# BluetoothBoard.net
KiCad netlist of a schematic drawn in EAGLE
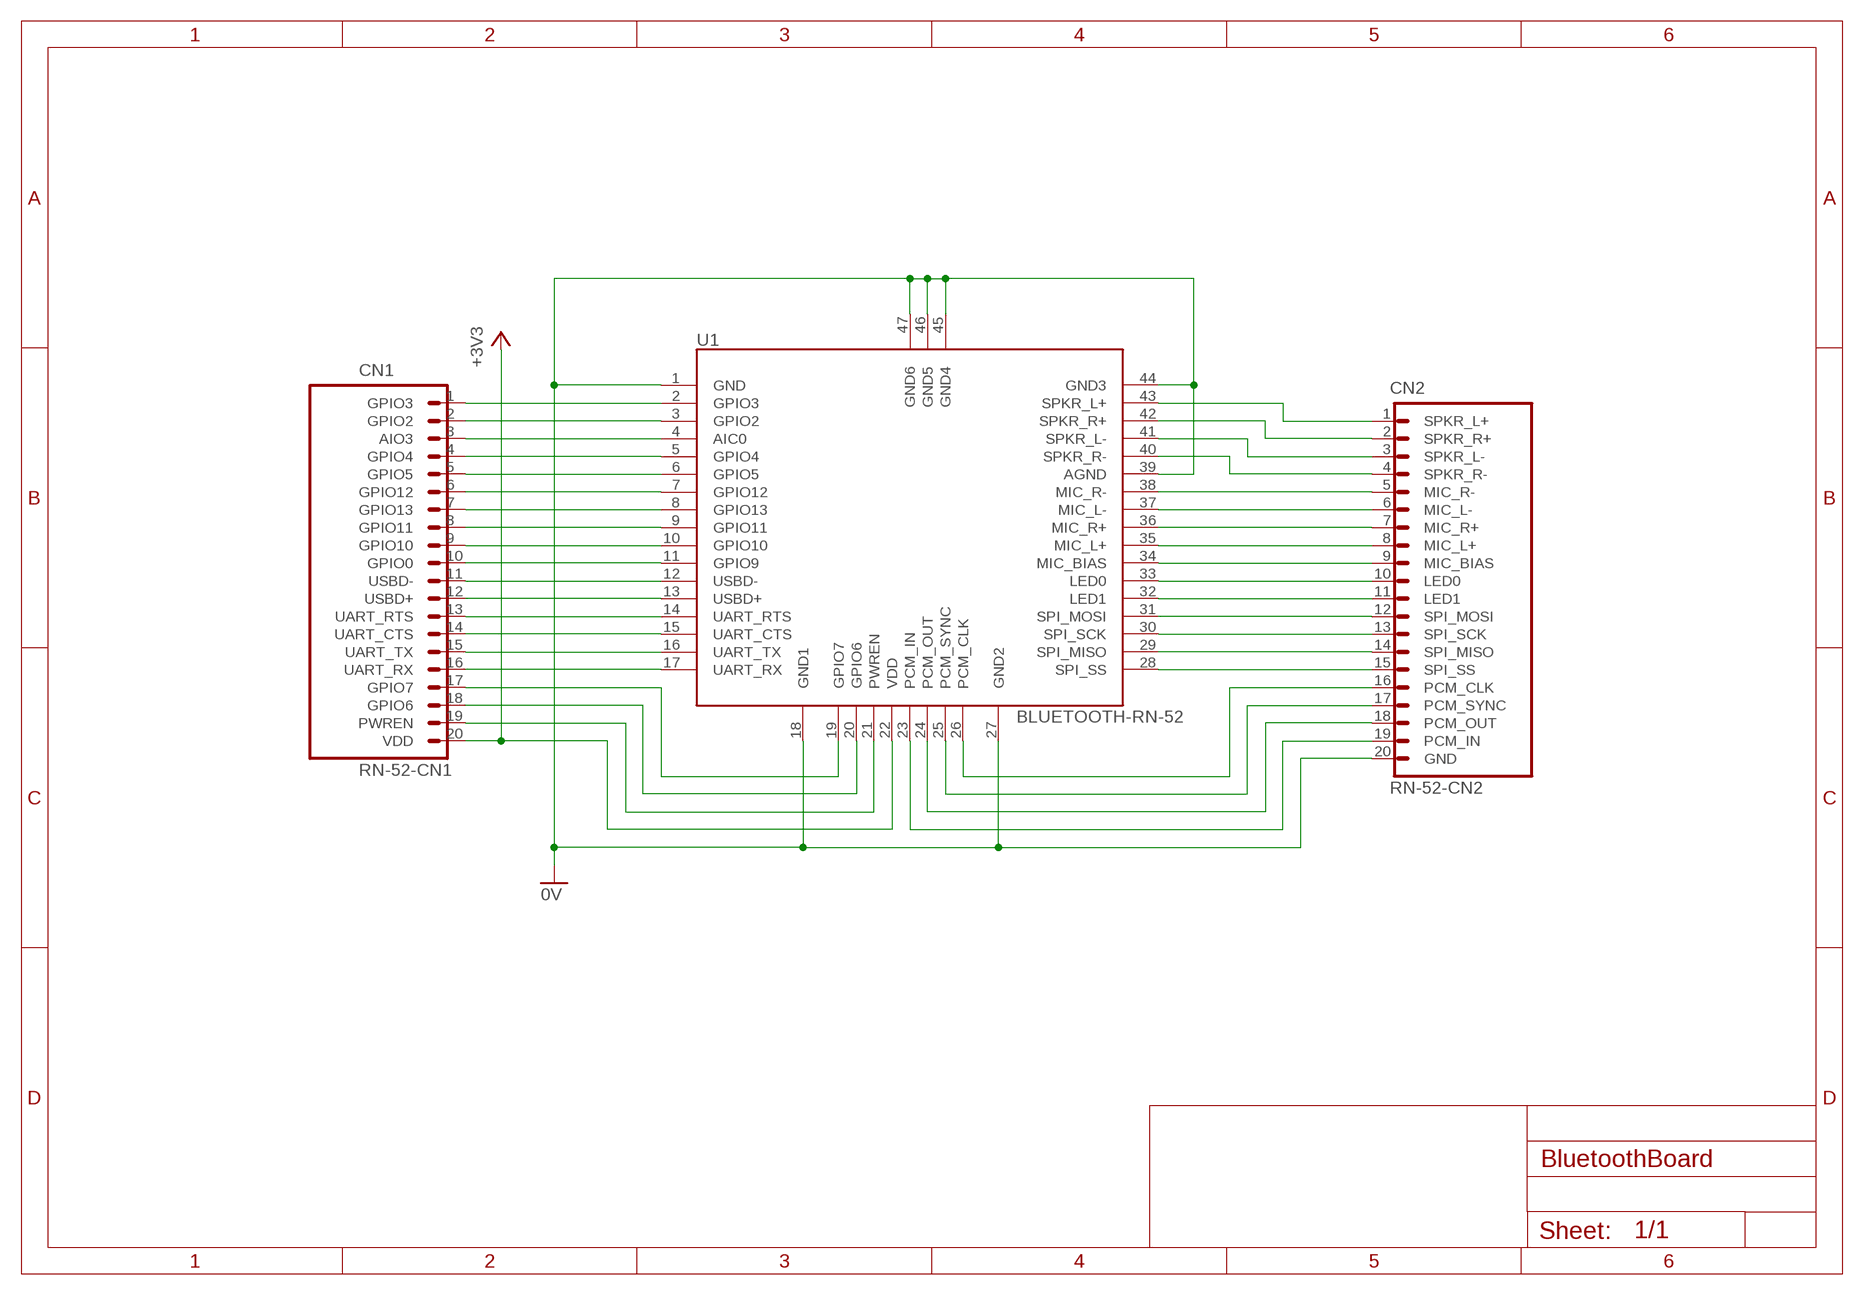
[diagram p0: schematic, sheet 1]

(export (version "E")
  (design (tool "Eeschema 10.0.6"))
  (components
    (comp (ref "CN1")
      (value "RN-52-CN1")
      (footprint "eagle-import:RN-52-CN1")
      (libsource (lib "eagle-import") (part "RN-52-CN1"))
    )
    (comp (ref "CN2")
      (value "RN-52-CN2")
      (footprint "eagle-import:RN-52-CN2")
      (libsource (lib "eagle-import") (part "RN-52-CN2"))
    )
    (comp (ref "U1")
      (value "BLUETOOTH-RN-52")
      (footprint "eagle-import:RN-52")
      (libsource (lib "eagle-import") (part "BLUETOOTH-RN-52"))
    )
  )
  (nets
    (net (code "1") (name "+3V3") (class "Default")
      (node (ref "CN1") (pin "20") (pinfunction "VDD_20") (pintype "bidirectional"))
      (node (ref "U1") (pin "22") (pinfunction "VDD_22") (pintype "passive"))
    )
    (net (code "2") (name "0V") (class "Default")
      (node (ref "CN2") (pin "20") (pinfunction "GND_20") (pintype "bidirectional"))
      (node (ref "U1") (pin "1") (pinfunction "GND_1") (pintype "passive"))
      (node (ref "U1") (pin "18") (pinfunction "GND1_18") (pintype "passive"))
      (node (ref "U1") (pin "27") (pinfunction "GND2_27") (pintype "passive"))
      (node (ref "U1") (pin "39") (pinfunction "AGND_39") (pintype "passive"))
      (node (ref "U1") (pin "44") (pinfunction "GND3_44") (pintype "passive"))
      (node (ref "U1") (pin "45") (pinfunction "GND4_45") (pintype "passive"))
      (node (ref "U1") (pin "46") (pinfunction "GND5_46") (pintype "passive"))
      (node (ref "U1") (pin "47") (pinfunction "GND6_47") (pintype "passive"))
    )
    (net (code "3") (name "Net-(CN1-AIO3)") (class "Default")
      (node (ref "CN1") (pin "3") (pinfunction "AIO3_3") (pintype "bidirectional"))
      (node (ref "U1") (pin "4") (pinfunction "AIC0_4") (pintype "bidirectional"))
    )
    (net (code "4") (name "Net-(CN1-GPIO0)") (class "Default")
      (node (ref "CN1") (pin "10") (pinfunction "GPIO0_10") (pintype "bidirectional"))
      (node (ref "U1") (pin "11") (pinfunction "GPIO9_11") (pintype "bidirectional"))
    )
    (net (code "5") (name "Net-(CN1-GPIO2)") (class "Default")
      (node (ref "CN1") (pin "2") (pinfunction "GPIO2_2") (pintype "bidirectional"))
      (node (ref "U1") (pin "3") (pinfunction "GPIO2_3") (pintype "bidirectional"))
    )
    (net (code "6") (name "Net-(CN1-GPIO3)") (class "Default")
      (node (ref "CN1") (pin "1") (pinfunction "GPIO3_1") (pintype "bidirectional"))
      (node (ref "U1") (pin "2") (pinfunction "GPIO3_2") (pintype "bidirectional"))
    )
    (net (code "7") (name "Net-(CN1-GPIO4)") (class "Default")
      (node (ref "CN1") (pin "4") (pinfunction "GPIO4_4") (pintype "bidirectional"))
      (node (ref "U1") (pin "5") (pinfunction "GPIO4_5") (pintype "bidirectional"))
    )
    (net (code "8") (name "Net-(CN1-GPIO5)") (class "Default")
      (node (ref "CN1") (pin "5") (pinfunction "GPIO5_5") (pintype "bidirectional"))
      (node (ref "U1") (pin "6") (pinfunction "GPIO5_6") (pintype "bidirectional"))
    )
    (net (code "9") (name "Net-(CN1-GPIO6)") (class "Default")
      (node (ref "CN1") (pin "18") (pinfunction "GPIO6_18") (pintype "bidirectional"))
      (node (ref "U1") (pin "20") (pinfunction "GPIO6_20") (pintype "bidirectional"))
    )
    (net (code "10") (name "Net-(CN1-GPIO7)") (class "Default")
      (node (ref "CN1") (pin "17") (pinfunction "GPIO7_17") (pintype "bidirectional"))
      (node (ref "U1") (pin "19") (pinfunction "GPIO7_19") (pintype "bidirectional"))
    )
    (net (code "11") (name "Net-(CN1-GPIO10)") (class "Default")
      (node (ref "CN1") (pin "9") (pinfunction "GPIO10_9") (pintype "bidirectional"))
      (node (ref "U1") (pin "10") (pinfunction "GPIO10_10") (pintype "bidirectional"))
    )
    (net (code "12") (name "Net-(CN1-GPIO11)") (class "Default")
      (node (ref "CN1") (pin "8") (pinfunction "GPIO11_8") (pintype "bidirectional"))
      (node (ref "U1") (pin "9") (pinfunction "GPIO11_9") (pintype "bidirectional"))
    )
    (net (code "13") (name "Net-(CN1-GPIO12)") (class "Default")
      (node (ref "CN1") (pin "6") (pinfunction "GPIO12_6") (pintype "bidirectional"))
      (node (ref "U1") (pin "7") (pinfunction "GPIO12_7") (pintype "bidirectional"))
    )
    (net (code "14") (name "Net-(CN1-GPIO13)") (class "Default")
      (node (ref "CN1") (pin "7") (pinfunction "GPIO13_7") (pintype "bidirectional"))
      (node (ref "U1") (pin "8") (pinfunction "GPIO13_8") (pintype "bidirectional"))
    )
    (net (code "15") (name "Net-(CN1-PWREN)") (class "Default")
      (node (ref "CN1") (pin "19") (pinfunction "PWREN_19") (pintype "bidirectional"))
      (node (ref "U1") (pin "21") (pinfunction "PWREN_21") (pintype "bidirectional"))
    )
    (net (code "16") (name "Net-(CN1-UART_CTS)") (class "Default")
      (node (ref "CN1") (pin "14") (pinfunction "UART_CTS_14") (pintype "bidirectional"))
      (node (ref "U1") (pin "15") (pinfunction "UART_CTS_15") (pintype "bidirectional"))
    )
    (net (code "17") (name "Net-(CN1-UART_RTS)") (class "Default")
      (node (ref "CN1") (pin "13") (pinfunction "UART_RTS_13") (pintype "bidirectional"))
      (node (ref "U1") (pin "14") (pinfunction "UART_RTS_14") (pintype "bidirectional"))
    )
    (net (code "18") (name "Net-(CN1-UART_RX)") (class "Default")
      (node (ref "CN1") (pin "16") (pinfunction "UART_RX_16") (pintype "bidirectional"))
      (node (ref "U1") (pin "17") (pinfunction "UART_RX_17") (pintype "bidirectional"))
    )
    (net (code "19") (name "Net-(CN1-UART_TX)") (class "Default")
      (node (ref "CN1") (pin "15") (pinfunction "UART_TX_15") (pintype "bidirectional"))
      (node (ref "U1") (pin "16") (pinfunction "UART_TX_16") (pintype "bidirectional"))
    )
    (net (code "20") (name "Net-(CN1-USBD+)") (class "Default")
      (node (ref "CN1") (pin "12") (pinfunction "USBD+_12") (pintype "bidirectional"))
      (node (ref "U1") (pin "13") (pinfunction "USBD+_13") (pintype "bidirectional"))
    )
    (net (code "21") (name "Net-(CN1-USBD-)") (class "Default")
      (node (ref "CN1") (pin "11") (pinfunction "USBD-_11") (pintype "bidirectional"))
      (node (ref "U1") (pin "12") (pinfunction "USBD-_12") (pintype "bidirectional"))
    )
    (net (code "22") (name "Net-(CN2-LED0)") (class "Default")
      (node (ref "CN2") (pin "10") (pinfunction "LED0_10") (pintype "bidirectional"))
      (node (ref "U1") (pin "33") (pinfunction "LED0_33") (pintype "bidirectional"))
    )
    (net (code "23") (name "Net-(CN2-LED1)") (class "Default")
      (node (ref "CN2") (pin "11") (pinfunction "LED1_11") (pintype "bidirectional"))
      (node (ref "U1") (pin "32") (pinfunction "LED1_32") (pintype "bidirectional"))
    )
    (net (code "24") (name "Net-(CN2-MIC_BIAS)") (class "Default")
      (node (ref "CN2") (pin "9") (pinfunction "MIC_BIAS_9") (pintype "bidirectional"))
      (node (ref "U1") (pin "34") (pinfunction "MIC_BIAS_34") (pintype "bidirectional"))
    )
    (net (code "25") (name "Net-(CN2-MIC_L+)") (class "Default")
      (node (ref "CN2") (pin "8") (pinfunction "MIC_L+_8") (pintype "bidirectional"))
      (node (ref "U1") (pin "35") (pinfunction "MIC_L+_35") (pintype "bidirectional"))
    )
    (net (code "26") (name "Net-(CN2-MIC_L-)") (class "Default")
      (node (ref "CN2") (pin "6") (pinfunction "MIC_L-_6") (pintype "bidirectional"))
      (node (ref "U1") (pin "37") (pinfunction "MIC_L-_37") (pintype "bidirectional"))
    )
    (net (code "27") (name "Net-(CN2-MIC_R+)") (class "Default")
      (node (ref "CN2") (pin "7") (pinfunction "MIC_R+_7") (pintype "bidirectional"))
      (node (ref "U1") (pin "36") (pinfunction "MIC_R+_36") (pintype "bidirectional"))
    )
    (net (code "28") (name "Net-(CN2-MIC_R-)") (class "Default")
      (node (ref "CN2") (pin "5") (pinfunction "MIC_R-_5") (pintype "bidirectional"))
      (node (ref "U1") (pin "38") (pinfunction "MIC_R-_38") (pintype "bidirectional"))
    )
    (net (code "29") (name "Net-(CN2-PCM_CLK)") (class "Default")
      (node (ref "CN2") (pin "16") (pinfunction "PCM_CLK_16") (pintype "bidirectional"))
      (node (ref "U1") (pin "26") (pinfunction "PCM_CLK_26") (pintype "bidirectional"))
    )
    (net (code "30") (name "Net-(CN2-PCM_IN)") (class "Default")
      (node (ref "CN2") (pin "19") (pinfunction "PCM_IN_19") (pintype "bidirectional"))
      (node (ref "U1") (pin "23") (pinfunction "PCM_IN_23") (pintype "bidirectional"))
    )
    (net (code "31") (name "Net-(CN2-PCM_OUT)") (class "Default")
      (node (ref "CN2") (pin "18") (pinfunction "PCM_OUT_18") (pintype "bidirectional"))
      (node (ref "U1") (pin "24") (pinfunction "PCM_OUT_24") (pintype "bidirectional"))
    )
    (net (code "32") (name "Net-(CN2-PCM_SYNC)") (class "Default")
      (node (ref "CN2") (pin "17") (pinfunction "PCM_SYNC_17") (pintype "bidirectional"))
      (node (ref "U1") (pin "25") (pinfunction "PCM_SYNC_25") (pintype "bidirectional"))
    )
    (net (code "33") (name "Net-(CN2-SPI_MISO)") (class "Default")
      (node (ref "CN2") (pin "14") (pinfunction "SPI_MISO_14") (pintype "bidirectional"))
      (node (ref "U1") (pin "29") (pinfunction "SPI_MISO_29") (pintype "bidirectional"))
    )
    (net (code "34") (name "Net-(CN2-SPI_MOSI)") (class "Default")
      (node (ref "CN2") (pin "12") (pinfunction "SPI_MOSI_12") (pintype "bidirectional"))
      (node (ref "U1") (pin "31") (pinfunction "SPI_MOSI_31") (pintype "bidirectional"))
    )
    (net (code "35") (name "Net-(CN2-SPI_SCK)") (class "Default")
      (node (ref "CN2") (pin "13") (pinfunction "SPI_SCK_13") (pintype "bidirectional"))
      (node (ref "U1") (pin "30") (pinfunction "SPI_SCK_30") (pintype "bidirectional"))
    )
    (net (code "36") (name "Net-(CN2-SPI_SS)") (class "Default")
      (node (ref "CN2") (pin "15") (pinfunction "SPI_SS_15") (pintype "bidirectional"))
      (node (ref "U1") (pin "28") (pinfunction "SPI_SS_28") (pintype "bidirectional"))
    )
    (net (code "37") (name "Net-(CN2-SPKR_L+)") (class "Default")
      (node (ref "CN2") (pin "1") (pinfunction "SPKR_L+_1") (pintype "bidirectional"))
      (node (ref "U1") (pin "43") (pinfunction "SPKR_L+_43") (pintype "bidirectional"))
    )
    (net (code "38") (name "Net-(CN2-SPKR_L-)") (class "Default")
      (node (ref "CN2") (pin "3") (pinfunction "SPKR_L-_3") (pintype "bidirectional"))
      (node (ref "U1") (pin "41") (pinfunction "SPKR_L-_41") (pintype "bidirectional"))
    )
    (net (code "39") (name "Net-(CN2-SPKR_R+)") (class "Default")
      (node (ref "CN2") (pin "2") (pinfunction "SPKR_R+_2") (pintype "bidirectional"))
      (node (ref "U1") (pin "42") (pinfunction "SPKR_R+_42") (pintype "bidirectional"))
    )
    (net (code "40") (name "Net-(CN2-SPKR_R-)") (class "Default")
      (node (ref "CN2") (pin "4") (pinfunction "SPKR_R-_4") (pintype "bidirectional"))
      (node (ref "U1") (pin "40") (pinfunction "SPKR_R-_40") (pintype "bidirectional"))
    )
  )
)
